# dcshift_digital.net
KiCad netlist of a schematic drawn in Altium Designer
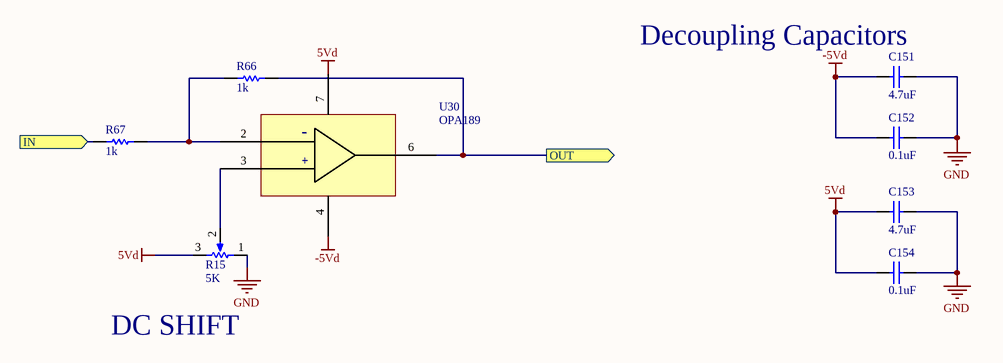
[diagram p0: dcshift_digital.SchDoc]

(export (version "E")
  (design (tool "Eeschema 10.0.6"))
  (components
    (comp (ref "C151")
      (value "4.7uF")
      (footprint "0402_Cap")
      (description "Capacitor, 4.7uF, 0805")
      (libsource (lib "Arturo_Approved") (part "CL21A475KAQNNNE"))
    )
    (comp (ref "C152")
      (value "0.1uF")
      (footprint "0402_Cap")
      (description "Capacitor, 0.1uF, 0805")
      (libsource (lib "Arturo_Approved") (part "CL21B104KACNNNC"))
    )
    (comp (ref "C153")
      (value "4.7uF")
      (footprint "0402_Cap")
      (description "Capacitor, 4.7uF, 0805")
      (libsource (lib "Arturo_Approved") (part "CL21A475KAQNNNE"))
    )
    (comp (ref "C154")
      (value "0.1uF")
      (footprint "0402_Cap")
      (description "Capacitor, 0.1uF, 0805")
      (libsource (lib "Arturo_Approved") (part "CL21B104KACNNNC"))
    )
    (comp (ref "R15")
      (value "5K")
      (footprint "TRIMPOT")
      (description "Potentiometer, 1k")
      (libsource (lib "Arturo_Approved") (part "PV36W102C01B00"))
    )
    (comp (ref "R66")
      (value "1k")
      (footprint "0402_Res")
      (description "1K 1% 1/4W")
      (libsource (lib "Arturo_Approved") (part "RNCP0805FTD1K00"))
    )
    (comp (ref "R67")
      (value "1k")
      (footprint "0402_Res")
      (description "1K 1% 1/4W")
      (libsource (lib "Arturo_Approved") (part "RNCP0805FTD1K00"))
    )
    (comp (ref "U30")
      (value "OPA189")
      (footprint "SOIC_8")
      (description "Precision OpAmp, Generic")
      (libsource (lib "Arturo_Approved") (part "OPA189IDR"))
    )
  )
  (nets
    (net (code "1") (name "-5Vd") (class "Default")
      (node (ref "C151") (pin "1") (pinfunction "1_1") (pintype "passive"))
      (node (ref "C152") (pin "1") (pinfunction "1_1") (pintype "passive"))
      (node (ref "U30") (pin "4") (pintype "passive"))
    )
    (net (code "2") (name "/IN") (class "Default")
      (node (ref "R67") (pin "1") (pinfunction "1_1") (pintype "passive"))
    )
    (net (code "3") (name "/OUT") (class "Default")
      (node (ref "R66") (pin "2") (pinfunction "2_2") (pintype "passive"))
      (node (ref "U30") (pin "6") (pintype "passive"))
    )
    (net (code "4") (name "5Vd") (class "Default")
      (node (ref "C153") (pin "1") (pinfunction "1_1") (pintype "passive"))
      (node (ref "C154") (pin "1") (pinfunction "1_1") (pintype "passive"))
      (node (ref "R15") (pin "3") (pinfunction "BOT_3") (pintype "passive"))
      (node (ref "U30") (pin "7") (pintype "passive"))
    )
    (net (code "5") (name "GND") (class "Default")
      (node (ref "C151") (pin "2") (pinfunction "2_2") (pintype "passive"))
      (node (ref "C152") (pin "2") (pinfunction "2_2") (pintype "passive"))
      (node (ref "C153") (pin "2") (pinfunction "2_2") (pintype "passive"))
      (node (ref "C154") (pin "2") (pinfunction "2_2") (pintype "passive"))
      (node (ref "R15") (pin "1") (pinfunction "TOP_1") (pintype "passive"))
    )
    (net (code "6") (name "Net-(R15-TAP)") (class "Default")
      (node (ref "R15") (pin "2") (pinfunction "TAP_2") (pintype "passive"))
      (node (ref "U30") (pin "3") (pintype "passive"))
    )
    (net (code "7") (name "Net-(R66-Pad1)") (class "Default")
      (node (ref "R66") (pin "1") (pinfunction "1_1") (pintype "passive"))
      (node (ref "R67") (pin "2") (pinfunction "2_2") (pintype "passive"))
      (node (ref "U30") (pin "2") (pintype "passive"))
    )
  )
)
